# Room485.net
KiCad netlist of a schematic drawn in Altium Designer
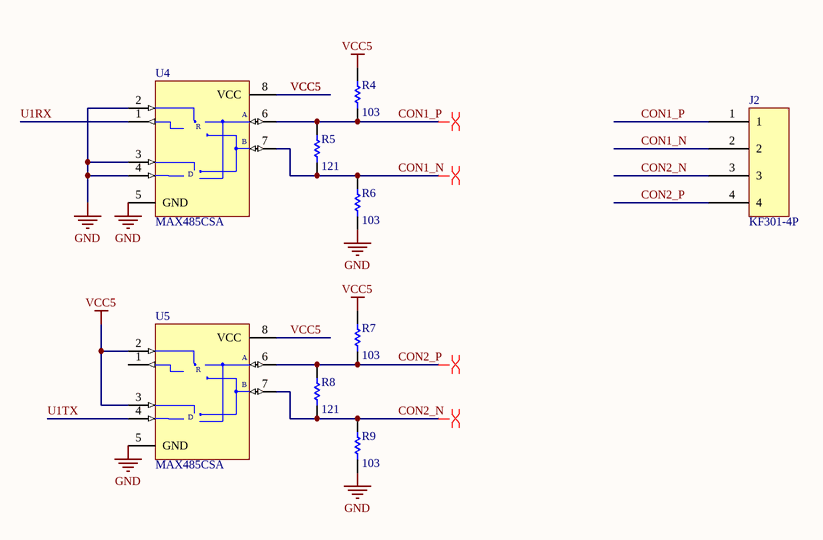
[diagram p0: Room485.SchDoc]

(export (version "E")
  (design (tool "Eeschema 10.0.6"))
  (components
    (comp (ref "J2") (value "KF301-4P") (footprint "KF301-4P") (libsource (lib "CHK-I") (part "KF301-4P")))
    (comp (ref "R4")
      (value "103")
      (footprint "RESC3216L")
      (description "Semiconductor Resistor")
      (fields (field (name "Comment") "Res Semi") (field (name "PUBLISHER") "Altium Limited"))
      (libsource (lib "Miscellaneous Devices") (part "Res Semi"))
    )
    (comp (ref "R5")
      (value "121")
      (footprint "RESC3216L")
      (description "Semiconductor Resistor")
      (fields (field (name "Comment") "Res Semi") (field (name "PUBLISHER") "Altium Limited"))
      (libsource (lib "Miscellaneous Devices") (part "Res Semi"))
    )
    (comp (ref "R6")
      (value "103")
      (footprint "RESC3216L")
      (description "Semiconductor Resistor")
      (fields (field (name "Comment") "Res Semi") (field (name "PUBLISHER") "Altium Limited"))
      (libsource (lib "Miscellaneous Devices") (part "Res Semi"))
    )
    (comp (ref "R7")
      (value "103")
      (footprint "RESC3216L")
      (description "Semiconductor Resistor")
      (fields (field (name "Comment") "Res Semi") (field (name "PUBLISHER") "Altium Limited"))
      (libsource (lib "Miscellaneous Devices") (part "Res Semi"))
    )
    (comp (ref "R8")
      (value "121")
      (footprint "RESC3216L")
      (description "Semiconductor Resistor")
      (fields (field (name "Comment") "Res Semi") (field (name "PUBLISHER") "Altium Limited"))
      (libsource (lib "Miscellaneous Devices") (part "Res Semi"))
    )
    (comp (ref "R9")
      (value "103")
      (footprint "RESC3216L")
      (description "Semiconductor Resistor")
      (fields (field (name "Comment") "Res Semi") (field (name "PUBLISHER") "Altium Limited"))
      (libsource (lib "Miscellaneous Devices") (part "Res Semi"))
    )
    (comp (ref "U4")
      (value "MAX485CSA")
      (footprint "NSO8_N")
      (description "Low-Power, Slew-Rate-Limited RS-485/RS-422 Transceiver")
      (fields (field (name "PUBLISHER") "Altium Limited"))
      (libsource (lib "Maxim Communication Transceiver") (part "MAX485CSA"))
    )
    (comp (ref "U5")
      (value "MAX485CSA")
      (footprint "NSO8_N")
      (description "Low-Power, Slew-Rate-Limited RS-485/RS-422 Transceiver")
      (fields (field (name "PUBLISHER") "Altium Limited"))
      (libsource (lib "Maxim Communication Transceiver") (part "MAX485CSA"))
    )
  )
  (nets
    (net (code "1") (name "/CON1_N") (class "Default")
      (node (ref "J2") (pin "2") (pinfunction "2_2") (pintype "passive"))
      (node (ref "R5") (pin "1") (pinfunction "1_1") (pintype "passive"))
      (node (ref "R6") (pin "2") (pinfunction "2_2") (pintype "passive"))
      (node (ref "U4") (pin "7") (pinfunction "B_7") (pintype "bidirectional"))
    )
    (net (code "2") (name "/CON1_P") (class "Default")
      (node (ref "J2") (pin "1") (pinfunction "1_1") (pintype "passive"))
      (node (ref "R4") (pin "1") (pinfunction "1_1") (pintype "passive"))
      (node (ref "R5") (pin "2") (pinfunction "2_2") (pintype "passive"))
      (node (ref "U4") (pin "6") (pinfunction "A_6") (pintype "bidirectional"))
    )
    (net (code "3") (name "/CON2_N") (class "Default")
      (node (ref "J2") (pin "3") (pinfunction "3_3") (pintype "passive"))
      (node (ref "R8") (pin "1") (pinfunction "1_1") (pintype "passive"))
      (node (ref "R9") (pin "2") (pinfunction "2_2") (pintype "passive"))
      (node (ref "U5") (pin "7") (pinfunction "B_7") (pintype "bidirectional"))
    )
    (net (code "4") (name "/CON2_P") (class "Default")
      (node (ref "J2") (pin "4") (pinfunction "4_4") (pintype "passive"))
      (node (ref "R7") (pin "1") (pinfunction "1_1") (pintype "passive"))
      (node (ref "R8") (pin "2") (pinfunction "2_2") (pintype "passive"))
      (node (ref "U5") (pin "6") (pinfunction "A_6") (pintype "bidirectional"))
    )
    (net (code "5") (name "/U1RX") (class "Default")
      (node (ref "U4") (pin "1") (pinfunction "RO_1") (pintype "output"))
    )
    (net (code "6") (name "/U1TX") (class "Default")
      (node (ref "U5") (pin "4") (pinfunction "DI_4") (pintype "input"))
    )
    (net (code "7") (name "GND") (class "Default")
      (node (ref "R6") (pin "1") (pinfunction "1_1") (pintype "passive"))
      (node (ref "R9") (pin "1") (pinfunction "1_1") (pintype "passive"))
      (node (ref "U4") (pin "2") (pinfunction "~{RE}_2") (pintype "input"))
      (node (ref "U4") (pin "3") (pinfunction "DE_3") (pintype "input"))
      (node (ref "U4") (pin "4") (pinfunction "DI_4") (pintype "input"))
      (node (ref "U4") (pin "5") (pinfunction "GND_5") (pintype "power_in"))
      (node (ref "U5") (pin "5") (pinfunction "GND_5") (pintype "power_in"))
    )
    (net (code "8") (name "VCC5") (class "Default")
      (node (ref "R4") (pin "2") (pinfunction "2_2") (pintype "passive"))
      (node (ref "R7") (pin "2") (pinfunction "2_2") (pintype "passive"))
      (node (ref "U4") (pin "8") (pinfunction "VCC_8") (pintype "power_in"))
      (node (ref "U5") (pin "2") (pinfunction "~{RE}_2") (pintype "input"))
      (node (ref "U5") (pin "3") (pinfunction "DE_3") (pintype "input"))
      (node (ref "U5") (pin "8") (pinfunction "VCC_8") (pintype "power_in"))
    )
    (net (code "9") (name "unconnected-(U5-RO-Pad1)") (class "Default")
      (node (ref "U5") (pin "1") (pinfunction "RO_1") (pintype "output"))
    )
  )
)
